# automation_node.net
KiCad netlist of a schematic drawn in EAGLE
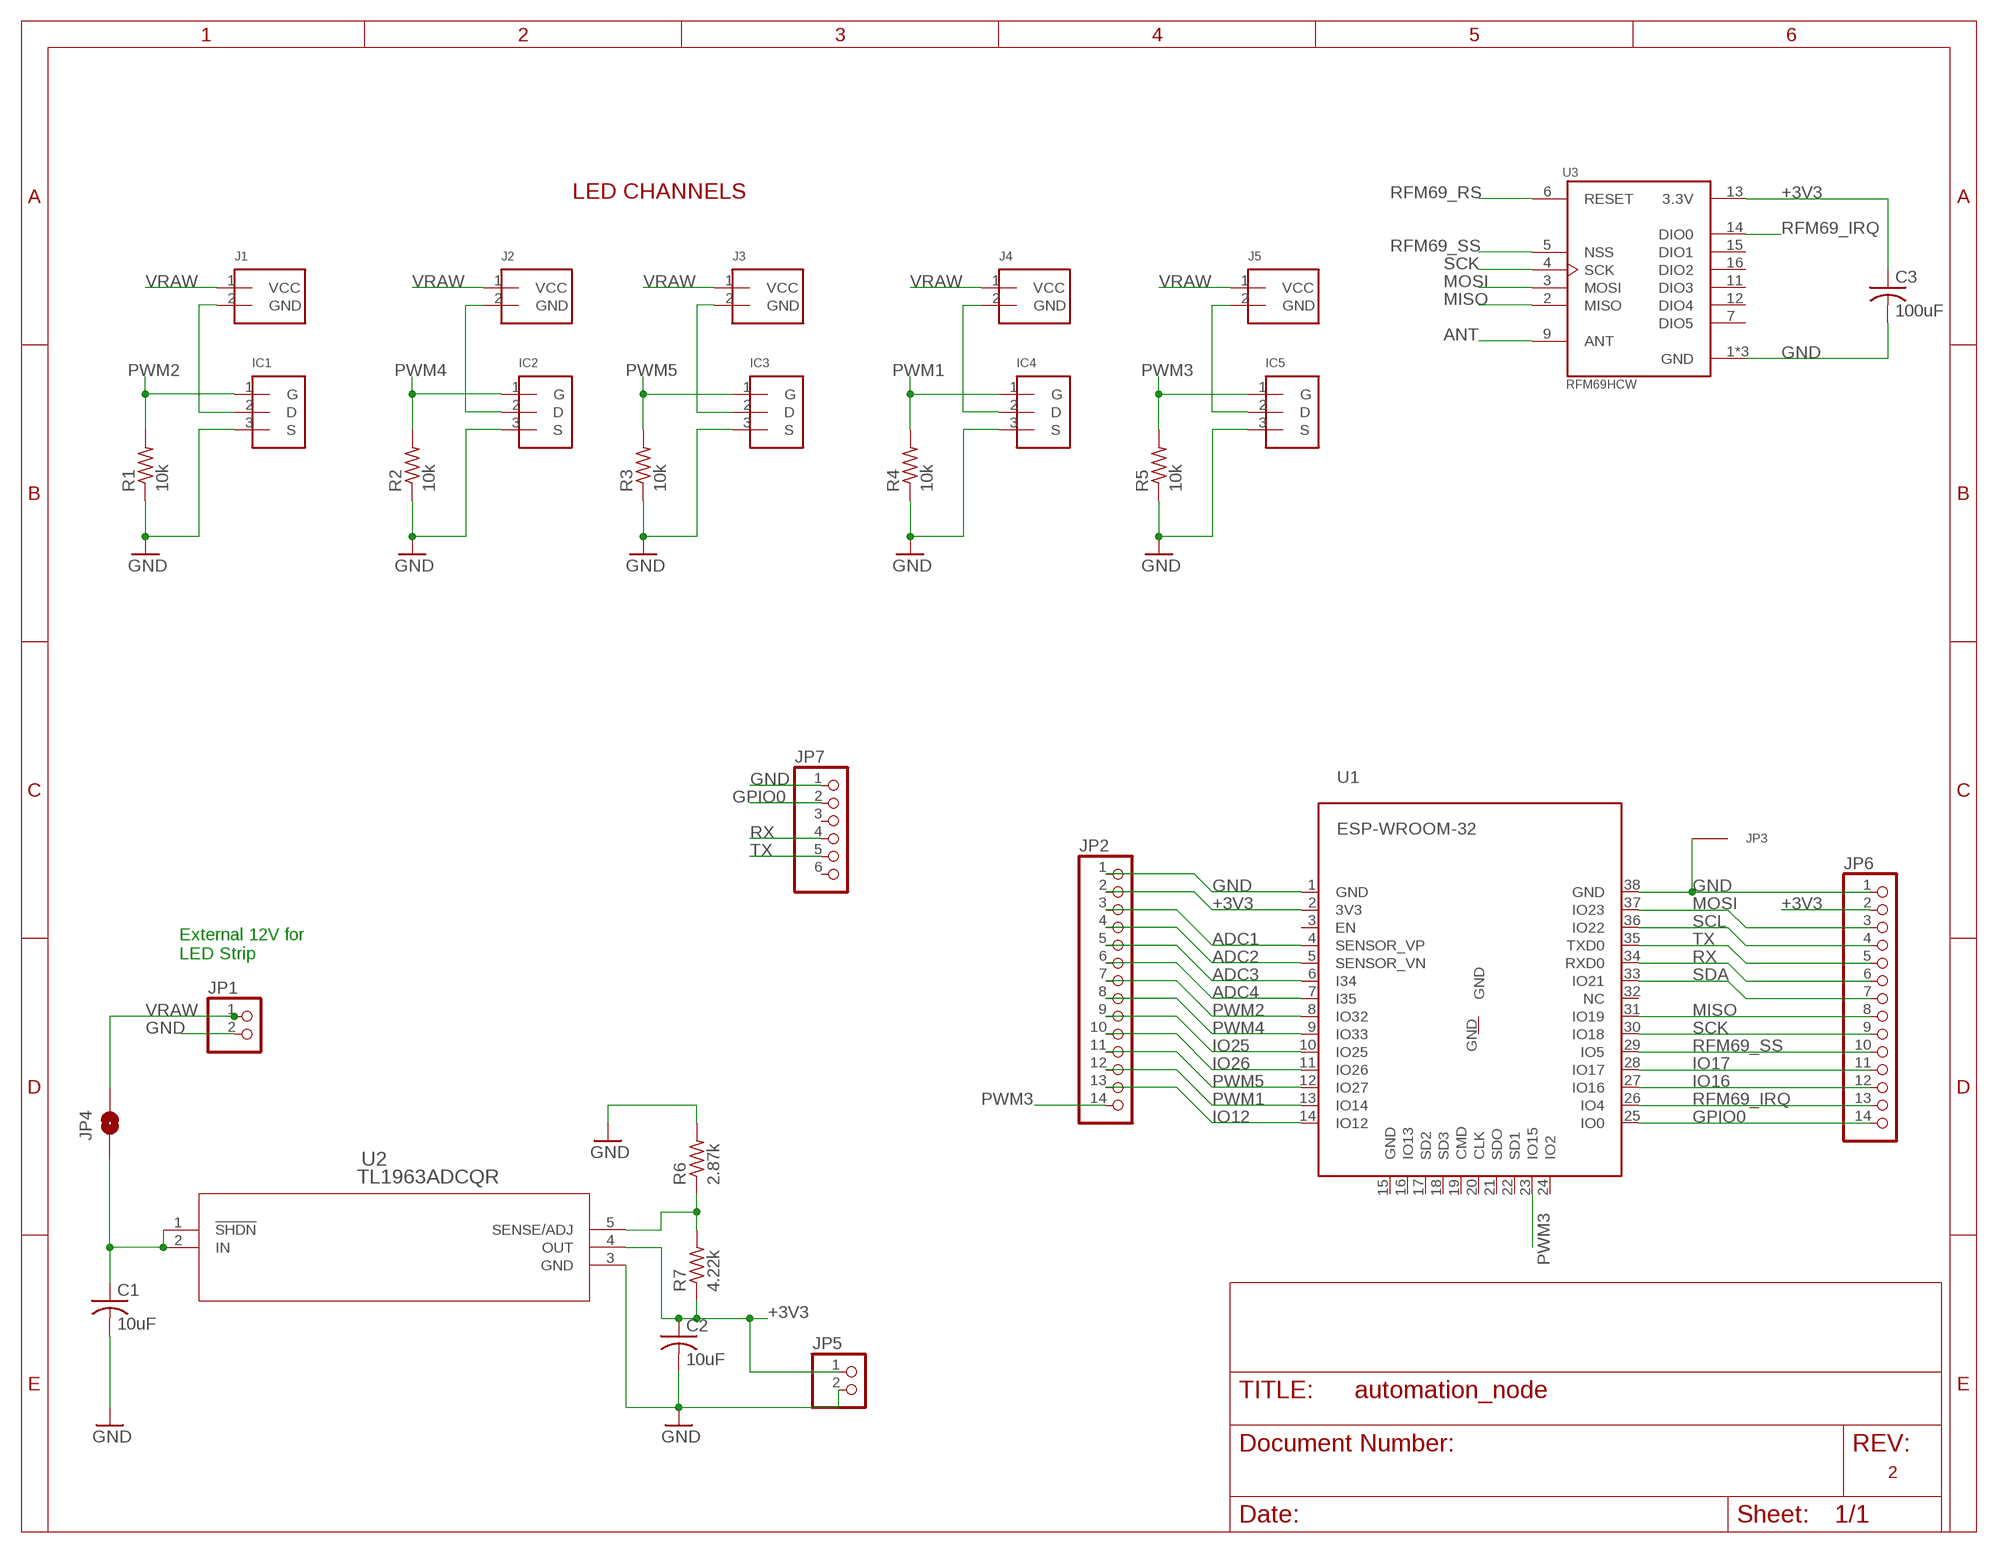
[diagram p0: schematic, sheet 1]

(export (version "E")
  (design (tool "Eeschema 10.0.6"))
  (components
    (comp (ref "C1")
      (value "10uF")
      (footprint "eagle-import:C0805")
      (libsource (lib "eagle-import") (part "C-USC0805"))
    )
    (comp (ref "C2")
      (value "10uF")
      (footprint "eagle-import:C0805")
      (libsource (lib "eagle-import") (part "C-USC0805"))
    )
    (comp (ref "C3")
      (value "100uF")
      (footprint "eagle-import:C0805")
      (libsource (lib "eagle-import") (part "C-USC0805"))
    )
    (comp (ref "IC1")
      (value "POWER_FET")
      (footprint "eagle-import:POWER_FET")
      (libsource (lib "eagle-import") (part "POWER_FET"))
    )
    (comp (ref "IC2")
      (value "POWER_FET")
      (footprint "eagle-import:POWER_FET")
      (libsource (lib "eagle-import") (part "POWER_FET"))
    )
    (comp (ref "IC3")
      (value "POWER_FET")
      (footprint "eagle-import:POWER_FET")
      (libsource (lib "eagle-import") (part "POWER_FET"))
    )
    (comp (ref "IC4")
      (value "POWER_FET")
      (footprint "eagle-import:POWER_FET")
      (libsource (lib "eagle-import") (part "POWER_FET"))
    )
    (comp (ref "IC5")
      (value "POWER_FET")
      (footprint "eagle-import:POWER_FET")
      (libsource (lib "eagle-import") (part "POWER_FET"))
    )
    (comp (ref "J1")
      (value "POWER-VIAS")
      (footprint "eagle-import:2CT-VIAS")
      (libsource (lib "eagle-import") (part "POWER-VIAS"))
    )
    (comp (ref "J2")
      (value "POWER-VIAS")
      (footprint "eagle-import:2CT-VIAS")
      (libsource (lib "eagle-import") (part "POWER-VIAS"))
    )
    (comp (ref "J3")
      (value "POWER-VIAS")
      (footprint "eagle-import:2CT-VIAS")
      (libsource (lib "eagle-import") (part "POWER-VIAS"))
    )
    (comp (ref "J4")
      (value "POWER-VIAS")
      (footprint "eagle-import:2CT-VIAS")
      (libsource (lib "eagle-import") (part "POWER-VIAS"))
    )
    (comp (ref "J5")
      (value "POWER-VIAS")
      (footprint "eagle-import:2CT-VIAS")
      (libsource (lib "eagle-import") (part "POWER-VIAS"))
    )
    (comp (ref "JP1")
      (value "PINHD-1X2")
      (footprint "eagle-import:1X02")
      (libsource (lib "eagle-import") (part "PINHD-1X2"))
    )
    (comp (ref "JP2")
      (value "PINHD-1X14")
      (footprint "eagle-import:1X14")
      (libsource (lib "eagle-import") (part "PINHD-1X14"))
    )
    (comp (ref "JP3")
      (value "PROTO_VIA_COMPACT")
      (footprint "eagle-import:PROTO_VIA")
      (libsource (lib "eagle-import") (part "PROTO_VIA_COMPACT"))
    )
    (comp (ref "JP4")
      (value "JUMPER-SMT_2_NO_SILK")
      (footprint "eagle-import:SMT-JUMPER_2_NO_SILK")
      (libsource (lib "eagle-import") (part "JUMPER-SMT_2_NO_SILK"))
    )
    (comp (ref "JP5")
      (value "PINHD-1X2")
      (footprint "eagle-import:1X02")
      (libsource (lib "eagle-import") (part "PINHD-1X2"))
    )
    (comp (ref "JP6")
      (value "PINHD-1X14")
      (footprint "eagle-import:1X14")
      (libsource (lib "eagle-import") (part "PINHD-1X14"))
    )
    (comp (ref "JP7")
      (value "PINHD-1X6")
      (footprint "eagle-import:1X06")
      (libsource (lib "eagle-import") (part "PINHD-1X6"))
    )
    (comp (ref "R1")
      (value "10k")
      (footprint "eagle-import:R0805")
      (libsource (lib "eagle-import") (part "R-US_R0805"))
    )
    (comp (ref "R2")
      (value "10k")
      (footprint "eagle-import:R0805")
      (libsource (lib "eagle-import") (part "R-US_R0805"))
    )
    (comp (ref "R3")
      (value "10k")
      (footprint "eagle-import:R0805")
      (libsource (lib "eagle-import") (part "R-US_R0805"))
    )
    (comp (ref "R4")
      (value "10k")
      (footprint "eagle-import:R0805")
      (libsource (lib "eagle-import") (part "R-US_R0805"))
    )
    (comp (ref "R5")
      (value "10k")
      (footprint "eagle-import:R0805")
      (libsource (lib "eagle-import") (part "R-US_R0805"))
    )
    (comp (ref "R6")
      (value "2.87k")
      (footprint "eagle-import:R0805")
      (libsource (lib "eagle-import") (part "R-US_R0805"))
    )
    (comp (ref "R7")
      (value "4.22k")
      (footprint "eagle-import:R0805")
      (libsource (lib "eagle-import") (part "R-US_R0805"))
    )
    (comp (ref "U1")
      (value "ESP-WROOM-32")
      (footprint "eagle-import:ESP-WROOM-32")
      (libsource (lib "eagle-import") (part "ESP-WROOM-32"))
    )
    (comp (ref "U2")
      (value "TL1963ADCQR")
      (footprint "eagle-import:DCQ6")
      (libsource (lib "eagle-import") (part "TL1963ADCQR"))
    )
    (comp (ref "U3")
      (value "RFM69HCW")
      (footprint "eagle-import:MOD_COM-13909")
      (fields (field (name "MF") "SparkFun Electronics") (field (name "MP") "COM-13909"))
      (libsource (lib "eagle-import") (part "RFM69HCW"))
    )
  )
  (nets
    (net (code "1") (name "/+3V3") (class "Default")
      (node (ref "C2") (pin "1") (pinfunction "1_1") (pintype "passive"))
      (node (ref "C3") (pin "1") (pinfunction "1_1") (pintype "passive"))
      (node (ref "JP2") (pin "2") (pinfunction "2_2") (pintype "passive"))
      (node (ref "JP5") (pin "1") (pinfunction "1_1") (pintype "passive"))
      (node (ref "JP6") (pin "2") (pinfunction "2_2") (pintype "passive"))
      (node (ref "R7") (pin "1") (pinfunction "1_1") (pintype "passive"))
      (node (ref "U1") (pin "2") (pinfunction "3V3_2") (pintype "bidirectional"))
      (node (ref "U2") (pin "4") (pinfunction "OUT_4") (pintype "output"))
      (node (ref "U3") (pin "13") (pinfunction "3.3V_13") (pintype "power_in"))
    )
    (net (code "2") (name "/ADC1") (class "Default")
      (node (ref "JP2") (pin "3") (pinfunction "3_3") (pintype "passive"))
      (node (ref "U1") (pin "4") (pinfunction "SENSOR_VP_4") (pintype "bidirectional"))
    )
    (net (code "3") (name "/ADC2") (class "Default")
      (node (ref "JP2") (pin "4") (pinfunction "4_4") (pintype "passive"))
      (node (ref "U1") (pin "5") (pinfunction "SENSOR_VN_5") (pintype "bidirectional"))
    )
    (net (code "4") (name "/ADC3") (class "Default")
      (node (ref "JP2") (pin "5") (pinfunction "5_5") (pintype "passive"))
      (node (ref "U1") (pin "6") (pinfunction "I34_6") (pintype "input"))
    )
    (net (code "5") (name "/ADC4") (class "Default")
      (node (ref "JP2") (pin "6") (pinfunction "6_6") (pintype "passive"))
      (node (ref "U1") (pin "7") (pinfunction "I35_7") (pintype "input"))
    )
    (net (code "6") (name "/ANT") (class "Default")
      (node (ref "U3") (pin "9") (pinfunction "ANT_9") (pintype "bidirectional"))
    )
    (net (code "7") (name "/GPIO0") (class "Default")
      (node (ref "JP6") (pin "14") (pinfunction "14_14") (pintype "passive"))
      (node (ref "JP7") (pin "2") (pinfunction "2_2") (pintype "passive"))
      (node (ref "U1") (pin "25") (pinfunction "IO0_25") (pintype "bidirectional"))
    )
    (net (code "8") (name "/IO12") (class "Default")
      (node (ref "JP2") (pin "13") (pinfunction "13_13") (pintype "passive"))
      (node (ref "U1") (pin "14") (pinfunction "IO12_14") (pintype "bidirectional"))
    )
    (net (code "9") (name "/IO16") (class "Default")
      (node (ref "JP6") (pin "12") (pinfunction "12_12") (pintype "passive"))
      (node (ref "U1") (pin "27") (pinfunction "IO16_27") (pintype "bidirectional"))
    )
    (net (code "10") (name "/IO17") (class "Default")
      (node (ref "JP6") (pin "11") (pinfunction "11_11") (pintype "passive"))
      (node (ref "U1") (pin "28") (pinfunction "IO17_28") (pintype "bidirectional"))
    )
    (net (code "11") (name "/IO25") (class "Default")
      (node (ref "JP2") (pin "9") (pinfunction "9_9") (pintype "passive"))
      (node (ref "U1") (pin "10") (pinfunction "IO25_10") (pintype "bidirectional"))
    )
    (net (code "12") (name "/IO26") (class "Default")
      (node (ref "JP2") (pin "10") (pinfunction "10_10") (pintype "passive"))
      (node (ref "U1") (pin "11") (pinfunction "IO26_11") (pintype "bidirectional"))
    )
    (net (code "13") (name "/MISO") (class "Default")
      (node (ref "JP6") (pin "8") (pinfunction "8_8") (pintype "passive"))
      (node (ref "U1") (pin "31") (pinfunction "IO19_31") (pintype "bidirectional"))
      (node (ref "U3") (pin "2") (pinfunction "MISO_2") (pintype "input"))
    )
    (net (code "14") (name "/MOSI") (class "Default")
      (node (ref "JP6") (pin "3") (pinfunction "3_3") (pintype "passive"))
      (node (ref "U1") (pin "37") (pinfunction "IO23_37") (pintype "bidirectional"))
      (node (ref "U3") (pin "3") (pinfunction "MOSI_3") (pintype "output"))
    )
    (net (code "15") (name "/PWM1") (class "Default")
      (node (ref "IC4") (pin "1") (pinfunction "G_1") (pintype "bidirectional"))
      (node (ref "JP2") (pin "12") (pinfunction "12_12") (pintype "passive"))
      (node (ref "R4") (pin "2") (pinfunction "2_2") (pintype "passive"))
      (node (ref "U1") (pin "13") (pinfunction "IO14_13") (pintype "bidirectional"))
    )
    (net (code "16") (name "/PWM2") (class "Default")
      (node (ref "IC1") (pin "1") (pinfunction "G_1") (pintype "bidirectional"))
      (node (ref "JP2") (pin "7") (pinfunction "7_7") (pintype "passive"))
      (node (ref "R1") (pin "2") (pinfunction "2_2") (pintype "passive"))
      (node (ref "U1") (pin "8") (pinfunction "IO32_8") (pintype "bidirectional"))
    )
    (net (code "17") (name "/PWM3") (class "Default")
      (node (ref "IC5") (pin "1") (pinfunction "G_1") (pintype "bidirectional"))
      (node (ref "JP2") (pin "14") (pinfunction "14_14") (pintype "passive"))
      (node (ref "R5") (pin "2") (pinfunction "2_2") (pintype "passive"))
      (node (ref "U1") (pin "23") (pinfunction "IO15_23") (pintype "bidirectional"))
    )
    (net (code "18") (name "/PWM4") (class "Default")
      (node (ref "IC2") (pin "1") (pinfunction "G_1") (pintype "bidirectional"))
      (node (ref "JP2") (pin "8") (pinfunction "8_8") (pintype "passive"))
      (node (ref "R2") (pin "2") (pinfunction "2_2") (pintype "passive"))
      (node (ref "U1") (pin "9") (pinfunction "IO33_9") (pintype "bidirectional"))
    )
    (net (code "19") (name "/PWM5") (class "Default")
      (node (ref "IC3") (pin "1") (pinfunction "G_1") (pintype "bidirectional"))
      (node (ref "JP2") (pin "11") (pinfunction "11_11") (pintype "passive"))
      (node (ref "R3") (pin "2") (pinfunction "2_2") (pintype "passive"))
      (node (ref "U1") (pin "12") (pinfunction "IO27_12") (pintype "bidirectional"))
    )
    (net (code "20") (name "/RFM69_IRQ") (class "Default")
      (node (ref "JP6") (pin "13") (pinfunction "13_13") (pintype "passive"))
      (node (ref "U1") (pin "26") (pinfunction "IO4_26") (pintype "bidirectional"))
      (node (ref "U3") (pin "14") (pinfunction "DIO0_14") (pintype "bidirectional"))
    )
    (net (code "21") (name "/RFM69_RS") (class "Default")
      (node (ref "U3") (pin "6") (pinfunction "RESET_6") (pintype "bidirectional"))
    )
    (net (code "22") (name "/RFM69_SS") (class "Default")
      (node (ref "JP6") (pin "10") (pinfunction "10_10") (pintype "passive"))
      (node (ref "U1") (pin "29") (pinfunction "IO5_29") (pintype "bidirectional"))
      (node (ref "U3") (pin "5") (pinfunction "NSS_5") (pintype "input"))
    )
    (net (code "23") (name "/RX") (class "Default")
      (node (ref "JP6") (pin "6") (pinfunction "6_6") (pintype "passive"))
      (node (ref "JP7") (pin "4") (pinfunction "4_4") (pintype "passive"))
      (node (ref "U1") (pin "34") (pinfunction "RXD0_34") (pintype "bidirectional"))
    )
    (net (code "24") (name "/SCK") (class "Default")
      (node (ref "JP6") (pin "9") (pinfunction "9_9") (pintype "passive"))
      (node (ref "U1") (pin "30") (pinfunction "IO18_30") (pintype "bidirectional"))
      (node (ref "U3") (pin "4") (pinfunction "SCK_4") (pintype "input"))
    )
    (net (code "25") (name "/SCL") (class "Default")
      (node (ref "JP6") (pin "4") (pinfunction "4_4") (pintype "passive"))
      (node (ref "U1") (pin "36") (pinfunction "IO22_36") (pintype "bidirectional"))
    )
    (net (code "26") (name "/SDA") (class "Default")
      (node (ref "JP6") (pin "7") (pinfunction "7_7") (pintype "passive"))
      (node (ref "U1") (pin "33") (pinfunction "IO21_33") (pintype "bidirectional"))
    )
    (net (code "27") (name "/TX") (class "Default")
      (node (ref "JP6") (pin "5") (pinfunction "5_5") (pintype "passive"))
      (node (ref "JP7") (pin "5") (pinfunction "5_5") (pintype "passive"))
      (node (ref "U1") (pin "35") (pinfunction "TXD0_35") (pintype "bidirectional"))
    )
    (net (code "28") (name "/VRAW") (class "Default")
      (node (ref "J1") (pin "1") (pinfunction "VCC_1") (pintype "bidirectional"))
      (node (ref "J2") (pin "1") (pinfunction "VCC_1") (pintype "bidirectional"))
      (node (ref "J3") (pin "1") (pinfunction "VCC_1") (pintype "bidirectional"))
      (node (ref "J4") (pin "1") (pinfunction "VCC_1") (pintype "bidirectional"))
      (node (ref "J5") (pin "1") (pinfunction "VCC_1") (pintype "bidirectional"))
      (node (ref "JP1") (pin "1") (pinfunction "1_1") (pintype "passive"))
      (node (ref "JP4") (pin "2") (pinfunction "2_2") (pintype "passive"))
    )
    (net (code "29") (name "GND") (class "Default")
      (node (ref "C1") (pin "2") (pinfunction "2_2") (pintype "passive"))
      (node (ref "C2") (pin "2") (pinfunction "2_2") (pintype "passive"))
      (node (ref "C3") (pin "2") (pinfunction "2_2") (pintype "passive"))
      (node (ref "IC1") (pin "3") (pinfunction "S_3") (pintype "power_in"))
      (node (ref "IC2") (pin "3") (pinfunction "S_3") (pintype "power_in"))
      (node (ref "IC3") (pin "3") (pinfunction "S_3") (pintype "power_in"))
      (node (ref "IC4") (pin "3") (pinfunction "S_3") (pintype "power_in"))
      (node (ref "IC5") (pin "3") (pinfunction "S_3") (pintype "power_in"))
      (node (ref "JP1") (pin "2") (pinfunction "2_2") (pintype "passive"))
      (node (ref "JP2") (pin "1") (pinfunction "1_1") (pintype "passive"))
      (node (ref "JP3") (pin "1") (pinfunction "1_1") (pintype "bidirectional"))
      (node (ref "JP5") (pin "2") (pinfunction "2_2") (pintype "passive"))
      (node (ref "JP6") (pin "1") (pinfunction "1_1") (pintype "passive"))
      (node (ref "JP7") (pin "1") (pinfunction "1_1") (pintype "passive"))
      (node (ref "R1") (pin "1") (pinfunction "1_1") (pintype "passive"))
      (node (ref "R2") (pin "1") (pinfunction "1_1") (pintype "passive"))
      (node (ref "R3") (pin "1") (pinfunction "1_1") (pintype "passive"))
      (node (ref "R4") (pin "1") (pinfunction "1_1") (pintype "passive"))
      (node (ref "R5") (pin "1") (pinfunction "1_1") (pintype "passive"))
      (node (ref "R6") (pin "2") (pinfunction "2_2") (pintype "passive"))
      (node (ref "U1") (pin "1") (pinfunction "GND_1") (pintype "bidirectional"))
      (node (ref "U1") (pin "38") (pinfunction "GND_38") (pintype "bidirectional"))
      (node (ref "U2") (pin "3") (pinfunction "GND_3") (pintype "power_in"))
      (node (ref "U3") (pin "1") (pinfunction "GND_1") (pintype "power_in"))
      (node (ref "U3") (pin "10") (pinfunction "GND_10") (pintype "power_in"))
      (node (ref "U3") (pin "8") (pinfunction "GND_8") (pintype "power_in"))
    )
    (net (code "30") (name "Net-(IC1-D)") (class "Default")
      (node (ref "IC1") (pin "2") (pinfunction "D_2") (pintype "power_in"))
      (node (ref "J1") (pin "2") (pinfunction "GND_2") (pintype "bidirectional"))
    )
    (net (code "31") (name "Net-(IC2-D)") (class "Default")
      (node (ref "IC2") (pin "2") (pinfunction "D_2") (pintype "power_in"))
      (node (ref "J2") (pin "2") (pinfunction "GND_2") (pintype "bidirectional"))
    )
    (net (code "32") (name "Net-(IC3-D)") (class "Default")
      (node (ref "IC3") (pin "2") (pinfunction "D_2") (pintype "power_in"))
      (node (ref "J3") (pin "2") (pinfunction "GND_2") (pintype "bidirectional"))
    )
    (net (code "33") (name "Net-(IC4-D)") (class "Default")
      (node (ref "IC4") (pin "2") (pinfunction "D_2") (pintype "power_in"))
      (node (ref "J4") (pin "2") (pinfunction "GND_2") (pintype "bidirectional"))
    )
    (net (code "34") (name "Net-(IC5-D)") (class "Default")
      (node (ref "IC5") (pin "2") (pinfunction "D_2") (pintype "power_in"))
      (node (ref "J5") (pin "2") (pinfunction "GND_2") (pintype "bidirectional"))
    )
    (net (code "35") (name "Net-(U2-IN)") (class "Default")
      (node (ref "C1") (pin "1") (pinfunction "1_1") (pintype "passive"))
      (node (ref "JP4") (pin "1") (pinfunction "1_1") (pintype "passive"))
      (node (ref "U2") (pin "1") (pinfunction "~{SHDN}_1") (pintype "passive"))
      (node (ref "U2") (pin "2") (pinfunction "IN_2") (pintype "input"))
    )
    (net (code "36") (name "Net-(U2-SENSE{slash}ADJ)") (class "Default")
      (node (ref "R6") (pin "1") (pinfunction "1_1") (pintype "passive"))
      (node (ref "R7") (pin "2") (pinfunction "2_2") (pintype "passive"))
      (node (ref "U2") (pin "5") (pinfunction "SENSE/ADJ_5") (pintype "passive"))
    )
    (net (code "37") (name "unconnected-(JP7-Pad3)") (class "Default")
      (node (ref "JP7") (pin "3") (pinfunction "3_3") (pintype "passive"))
    )
    (net (code "38") (name "unconnected-(JP7-Pad6)") (class "Default")
      (node (ref "JP7") (pin "6") (pinfunction "6_6") (pintype "passive"))
    )
    (net (code "39") (name "unconnected-(U1-CLK-Pad20)") (class "Default")
      (node (ref "U1") (pin "20") (pinfunction "CLK_20") (pintype "bidirectional"))
    )
    (net (code "40") (name "unconnected-(U1-CMD-Pad19)") (class "Default")
      (node (ref "U1") (pin "19") (pinfunction "CMD_19") (pintype "bidirectional"))
    )
    (net (code "41") (name "unconnected-(U1-EN-Pad3)") (class "Default")
      (node (ref "U1") (pin "3") (pinfunction "EN_3") (pintype "bidirectional"))
    )
    (net (code "42") (name "unconnected-(U1-GND-Pad15)") (class "Default")
      (node (ref "U1") (pin "15") (pinfunction "GND_15") (pintype "bidirectional"))
    )
    (net (code "43") (name "unconnected-(U1-IO2-Pad24)") (class "Default")
      (node (ref "U1") (pin "24") (pinfunction "IO2_24") (pintype "bidirectional"))
    )
    (net (code "44") (name "unconnected-(U1-IO13-Pad16)") (class "Default")
      (node (ref "U1") (pin "16") (pinfunction "IO13_16") (pintype "bidirectional"))
    )
    (net (code "45") (name "unconnected-(U1-NC-Pad32)") (class "Default")
      (node (ref "U1") (pin "32") (pinfunction "NC_32") (pintype "bidirectional"))
    )
    (net (code "46") (name "unconnected-(U1-PadGND)") (class "Default")
      (node (ref "U1") (pin "GND") (pinfunction "GND_GND") (pintype "bidirectional"))
    )
    (net (code "47") (name "unconnected-(U1-SD1-Pad22)") (class "Default")
      (node (ref "U1") (pin "22") (pinfunction "SD1_22") (pintype "bidirectional"))
    )
    (net (code "48") (name "unconnected-(U1-SD2-Pad17)") (class "Default")
      (node (ref "U1") (pin "17") (pinfunction "SD2_17") (pintype "bidirectional"))
    )
    (net (code "49") (name "unconnected-(U1-SD3-Pad18)") (class "Default")
      (node (ref "U1") (pin "18") (pinfunction "SD3_18") (pintype "bidirectional"))
    )
    (net (code "50") (name "unconnected-(U1-SDO-Pad21)") (class "Default")
      (node (ref "U1") (pin "21") (pinfunction "SDO_21") (pintype "bidirectional"))
    )
    (net (code "51") (name "unconnected-(U3-DIO1-Pad15)") (class "Default")
      (node (ref "U3") (pin "15") (pinfunction "DIO1_15") (pintype "bidirectional"))
    )
    (net (code "52") (name "unconnected-(U3-DIO2-Pad16)") (class "Default")
      (node (ref "U3") (pin "16") (pinfunction "DIO2_16") (pintype "bidirectional"))
    )
    (net (code "53") (name "unconnected-(U3-DIO3-Pad11)") (class "Default")
      (node (ref "U3") (pin "11") (pinfunction "DIO3_11") (pintype "bidirectional"))
    )
    (net (code "54") (name "unconnected-(U3-DIO4-Pad12)") (class "Default")
      (node (ref "U3") (pin "12") (pinfunction "DIO4_12") (pintype "bidirectional"))
    )
    (net (code "55") (name "unconnected-(U3-DIO5-Pad7)") (class "Default")
      (node (ref "U3") (pin "7") (pinfunction "DIO5_7") (pintype "bidirectional"))
    )
  )
)
